# ZigBee.net
KiCad netlist of a schematic drawn in Altium Designer
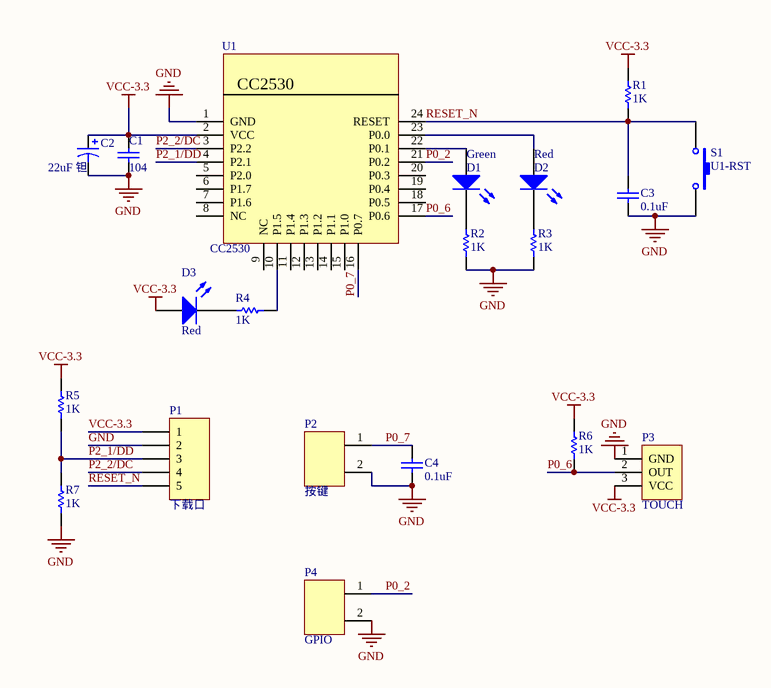
[diagram p0: 懒人关灯之_ZigBee终端电路.SchDoc]

(export (version "E")
  (design (tool "Eeschema 10.0.6"))
  (components
    (comp (ref "C1")
      (value "104")
      (footprint "0603")
      (description "Capacitor")
      (fields (field (name "Comment") "Cap") (field (name "PUBLISHER") "Altium Limited"))
      (libsource (lib "Miscellaneous Devices") (part "Cap"))
    )
    (comp (ref "C2")
      (value "22uF 钽")
      (footprint "CT2335-1210")
      (description "Polarized Capacitor (Radial)")
      (fields (field (name "Comment") "Cap Pol1") (field (name "PUBLISHER") "Altium Limited"))
      (libsource (lib "Miscellaneous Devices") (part "Cap Pol1"))
    )
    (comp (ref "C3")
      (value "0.1uF")
      (footprint "0603")
      (description "Capacitor")
      (fields (field (name "Comment") "Cap") (field (name "PUBLISHER") "Altium Limited"))
      (libsource (lib "Miscellaneous Devices") (part "Cap"))
    )
    (comp (ref "C4")
      (value "0.1uF")
      (footprint "0603")
      (description "Capacitor")
      (fields (field (name "Comment") "Cap") (field (name "PUBLISHER") "Altium Limited"))
      (libsource (lib "Miscellaneous Devices") (part "Cap"))
    )
    (comp (ref "D1")
      (value "Green")
      (footprint "0603-led")
      (description "Typical INFRARED GaAs LED")
      (fields (field (name "PUBLISHER") "Altium Limited"))
      (libsource (lib "Miscellaneous Devices") (part "LED0"))
    )
    (comp (ref "D2")
      (value "Red")
      (footprint "0603-led")
      (description "Typical INFRARED GaAs LED")
      (fields (field (name "PUBLISHER") "Altium Limited"))
      (libsource (lib "Miscellaneous Devices") (part "LED0"))
    )
    (comp (ref "D3")
      (value "Red")
      (footprint "0603-led")
      (description "Typical INFRARED GaAs LED")
      (fields (field (name "PUBLISHER") "Altium Limited"))
      (libsource (lib "Miscellaneous Devices") (part "LED0"))
    )
    (comp (ref "P1")
      (value "下载口")
      (footprint "5-PIN - zhen")
      (description "Header, 5-Pin")
      (fields (field (name "PUBLISHER") "Altium Limited"))
      (libsource (lib "Miscellaneous Connectors") (part "Header 5"))
    )
    (comp (ref "P2")
      (value "按键")
      (footprint "2-pin - duanzi - 3.81")
      (libsource (lib "教室信息终端") (part "2PIN"))
    )
    (comp (ref "P3")
      (value "TOUCH")
      (footprint "3PIN-TOUCH")
      (libsource (lib "懒人关灯之_ZigBee终端电路") (part "TOUCH"))
    )
    (comp (ref "P4") (value "GPIO") (footprint "2-pin") (libsource (lib "教室信息终端") (part "2PIN")))
    (comp (ref "R1")
      (value "1K")
      (footprint "0603")
      (description "Resistor")
      (fields (field (name "Comment") "Res1") (field (name "PUBLISHER") "Altium Limited"))
      (libsource (lib "Miscellaneous Devices") (part "Res1"))
    )
    (comp (ref "R2")
      (value "1K")
      (footprint "0603")
      (description "Resistor")
      (fields (field (name "Comment") "Res1") (field (name "PUBLISHER") "Altium Limited"))
      (libsource (lib "Miscellaneous Devices") (part "Res1"))
    )
    (comp (ref "R3")
      (value "1K")
      (footprint "0603")
      (description "Resistor")
      (fields (field (name "Comment") "Res1") (field (name "PUBLISHER") "Altium Limited"))
      (libsource (lib "Miscellaneous Devices") (part "Res1"))
    )
    (comp (ref "R4")
      (value "1K")
      (footprint "0603")
      (description "Resistor")
      (fields (field (name "Comment") "Res1") (field (name "PUBLISHER") "Altium Limited"))
      (libsource (lib "Miscellaneous Devices") (part "Res1"))
    )
    (comp (ref "R5")
      (value "1K")
      (footprint "0603")
      (description "Resistor")
      (fields (field (name "Comment") "Res1") (field (name "PUBLISHER") "Altium Limited"))
      (libsource (lib "Miscellaneous Devices") (part "Res1"))
    )
    (comp (ref "R6")
      (value "1K")
      (footprint "0603")
      (description "Resistor")
      (fields (field (name "Comment") "Res1") (field (name "PUBLISHER") "Altium Limited"))
      (libsource (lib "Miscellaneous Devices") (part "Res1"))
    )
    (comp (ref "R7")
      (value "1K")
      (footprint "0603")
      (description "Resistor")
      (fields (field (name "Comment") "Res1") (field (name "PUBLISHER") "Altium Limited"))
      (libsource (lib "Miscellaneous Devices") (part "Res1"))
    )
    (comp (ref "S1")
      (value "U1-RST")
      (footprint "K2-1806SA")
      (description "Switch")
      (fields (field (name "PUBLISHER") "Altium Limited"))
      (libsource (lib "Miscellaneous Devices") (part "SW-PB"))
    )
    (comp (ref "U1")
      (value "CC2530")
      (footprint "ZIGBEE-E18-MS1-PCB")
      (libsource (lib "懒人关灯之_ZigBee终端电路") (part "CC2530"))
    )
  )
  (nets
    (net (code "1") (name "/P0_2") (class "Default")
      (node (ref "P4") (pin "1") (pinfunction "1_1") (pintype "passive"))
      (node (ref "U1") (pin "21") (pinfunction "P0.2_21") (pintype "passive"))
    )
    (net (code "2") (name "/P0_6") (class "Default")
      (node (ref "P3") (pin "2") (pinfunction "OUT_2") (pintype "passive"))
      (node (ref "R6") (pin "2") (pinfunction "2_2") (pintype "passive"))
      (node (ref "U1") (pin "17") (pinfunction "P0.6_17") (pintype "passive"))
    )
    (net (code "3") (name "/P0_7") (class "Default")
      (node (ref "C4") (pin "1") (pinfunction "1_1") (pintype "passive"))
      (node (ref "P2") (pin "1") (pinfunction "1_1") (pintype "passive"))
      (node (ref "U1") (pin "16") (pinfunction "P0.7_16") (pintype "passive"))
    )
    (net (code "4") (name "/P2_1{slash}DD") (class "Default")
      (node (ref "P1") (pin "3") (pinfunction "3_3") (pintype "passive"))
      (node (ref "R5") (pin "2") (pinfunction "2_2") (pintype "passive"))
      (node (ref "R7") (pin "1") (pinfunction "1_1") (pintype "passive"))
      (node (ref "U1") (pin "4") (pinfunction "P2.1_4") (pintype "passive"))
    )
    (net (code "5") (name "/P2_2{slash}DC") (class "Default")
      (node (ref "P1") (pin "4") (pinfunction "4_4") (pintype "passive"))
      (node (ref "U1") (pin "3") (pinfunction "P2.2_3") (pintype "passive"))
    )
    (net (code "6") (name "/RESET_N") (class "Default")
      (node (ref "C3") (pin "1") (pinfunction "1_1") (pintype "passive"))
      (node (ref "P1") (pin "5") (pinfunction "5_5") (pintype "passive"))
      (node (ref "R1") (pin "2") (pinfunction "2_2") (pintype "passive"))
      (node (ref "S1") (pin "1") (pinfunction "1_1") (pintype "passive"))
      (node (ref "U1") (pin "24") (pinfunction "RESET_24") (pintype "passive"))
    )
    (net (code "7") (name "GND") (class "Default")
      (node (ref "C1") (pin "1") (pinfunction "1_1") (pintype "passive"))
      (node (ref "C2") (pin "2") (pinfunction "2_2") (pintype "passive"))
      (node (ref "C3") (pin "2") (pinfunction "2_2") (pintype "passive"))
      (node (ref "C4") (pin "2") (pinfunction "2_2") (pintype "passive"))
      (node (ref "P1") (pin "2") (pinfunction "2_2") (pintype "passive"))
      (node (ref "P2") (pin "2") (pinfunction "2_2") (pintype "passive"))
      (node (ref "P3") (pin "1") (pinfunction "GND_1") (pintype "passive"))
      (node (ref "P4") (pin "2") (pinfunction "2_2") (pintype "passive"))
      (node (ref "R2") (pin "2") (pinfunction "2_2") (pintype "passive"))
      (node (ref "R3") (pin "2") (pinfunction "2_2") (pintype "passive"))
      (node (ref "R7") (pin "2") (pinfunction "2_2") (pintype "passive"))
      (node (ref "S1") (pin "2") (pinfunction "2_2") (pintype "passive"))
      (node (ref "U1") (pin "1") (pinfunction "GND_1") (pintype "passive"))
    )
    (net (code "8") (name "Net-(D1-A)") (class "Default")
      (node (ref "D1") (pin "1") (pinfunction "A_1") (pintype "passive"))
      (node (ref "U1") (pin "22") (pinfunction "P0.1_22") (pintype "passive"))
    )
    (net (code "9") (name "Net-(D1-K)") (class "Default")
      (node (ref "D1") (pin "2") (pinfunction "K_2") (pintype "passive"))
      (node (ref "R2") (pin "1") (pinfunction "1_1") (pintype "passive"))
    )
    (net (code "10") (name "Net-(D2-A)") (class "Default")
      (node (ref "D2") (pin "1") (pinfunction "A_1") (pintype "passive"))
      (node (ref "U1") (pin "23") (pinfunction "P0.0_23") (pintype "passive"))
    )
    (net (code "11") (name "Net-(D2-K)") (class "Default")
      (node (ref "D2") (pin "2") (pinfunction "K_2") (pintype "passive"))
      (node (ref "R3") (pin "1") (pinfunction "1_1") (pintype "passive"))
    )
    (net (code "12") (name "Net-(D3-K)") (class "Default")
      (node (ref "D3") (pin "2") (pinfunction "K_2") (pintype "passive"))
      (node (ref "R4") (pin "1") (pinfunction "1_1") (pintype "passive"))
    )
    (net (code "13") (name "Net-(U1-P1.5)") (class "Default")
      (node (ref "R4") (pin "2") (pinfunction "2_2") (pintype "passive"))
      (node (ref "U1") (pin "10") (pinfunction "P1.5_10") (pintype "passive"))
    )
    (net (code "14") (name "VCC-3.3") (class "Default")
      (node (ref "C1") (pin "2") (pinfunction "2_2") (pintype "passive"))
      (node (ref "C2") (pin "1") (pinfunction "1_1") (pintype "passive"))
      (node (ref "D3") (pin "1") (pinfunction "A_1") (pintype "passive"))
      (node (ref "P1") (pin "1") (pinfunction "1_1") (pintype "passive"))
      (node (ref "P3") (pin "3") (pinfunction "VCC_3") (pintype "passive"))
      (node (ref "R1") (pin "1") (pinfunction "1_1") (pintype "passive"))
      (node (ref "R5") (pin "1") (pinfunction "1_1") (pintype "passive"))
      (node (ref "R6") (pin "1") (pinfunction "1_1") (pintype "passive"))
      (node (ref "U1") (pin "2") (pinfunction "VCC_2") (pintype "passive"))
    )
    (net (code "15") (name "unconnected-(U1-NC-Pad8)") (class "Default")
      (node (ref "U1") (pin "8") (pinfunction "NC_8") (pintype "passive"))
    )
    (net (code "16") (name "unconnected-(U1-NC-Pad9)") (class "Default")
      (node (ref "U1") (pin "9") (pinfunction "NC_9") (pintype "passive"))
    )
    (net (code "17") (name "unconnected-(U1-P0.3-Pad20)") (class "Default")
      (node (ref "U1") (pin "20") (pinfunction "P0.3_20") (pintype "passive"))
    )
    (net (code "18") (name "unconnected-(U1-P0.4-Pad19)") (class "Default")
      (node (ref "U1") (pin "19") (pinfunction "P0.4_19") (pintype "passive"))
    )
    (net (code "19") (name "unconnected-(U1-P0.5-Pad18)") (class "Default")
      (node (ref "U1") (pin "18") (pinfunction "P0.5_18") (pintype "passive"))
    )
    (net (code "20") (name "unconnected-(U1-P1.0-Pad15)") (class "Default")
      (node (ref "U1") (pin "15") (pinfunction "P1.0_15") (pintype "passive"))
    )
    (net (code "21") (name "unconnected-(U1-P1.1-Pad14)") (class "Default")
      (node (ref "U1") (pin "14") (pinfunction "P1.1_14") (pintype "passive"))
    )
    (net (code "22") (name "unconnected-(U1-P1.2-Pad13)") (class "Default")
      (node (ref "U1") (pin "13") (pinfunction "P1.2_13") (pintype "passive"))
    )
    (net (code "23") (name "unconnected-(U1-P1.3-Pad12)") (class "Default")
      (node (ref "U1") (pin "12") (pinfunction "P1.3_12") (pintype "passive"))
    )
    (net (code "24") (name "unconnected-(U1-P1.4-Pad11)") (class "Default")
      (node (ref "U1") (pin "11") (pinfunction "P1.4_11") (pintype "passive"))
    )
    (net (code "25") (name "unconnected-(U1-P1.6-Pad7)") (class "Default")
      (node (ref "U1") (pin "7") (pinfunction "P1.6_7") (pintype "passive"))
    )
    (net (code "26") (name "unconnected-(U1-P1.7-Pad6)") (class "Default")
      (node (ref "U1") (pin "6") (pinfunction "P1.7_6") (pintype "passive"))
    )
    (net (code "27") (name "unconnected-(U1-P2.0-Pad5)") (class "Default")
      (node (ref "U1") (pin "5") (pinfunction "P2.0_5") (pintype "passive"))
    )
  )
)
